# GD_Tcontroller_Sensor.net
KiCad netlist of a schematic drawn in Altium Designer
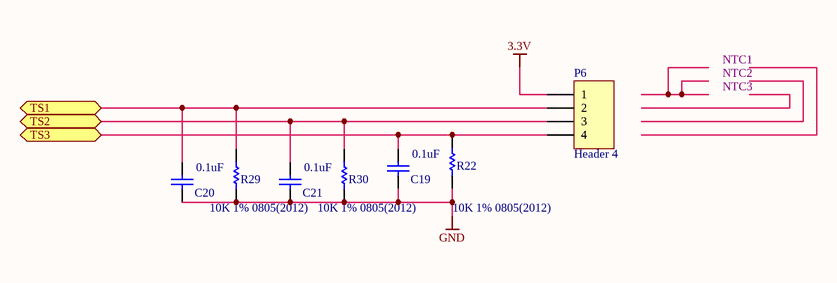
[diagram p0: GD_Tcontroller_Sensor.SchDoc]

(export (version "E")
  (design (tool "Eeschema 10.0.6"))
  (components
    (comp (ref "C19")
      (value "0.1uF")
      (footprint "CAPC0805(2012)100_N")
      (description "CAP 0.1uF 50V ±20% 0805 (2012 Metric) Thickness 1mm SMD")
      (fields (field (name "TOLERANCE") "20%") (field (name "Comment") "CAP 0.1uF 50V 0805(2012)"))
      (libsource (lib "Altium Content Vault") (part "CMP-1036-00070-1"))
    )
    (comp (ref "C20")
      (value "0.1uF")
      (footprint "CAPC0805(2012)100_N")
      (description "CAP 0.1uF 50V ±20% 0805 (2012 Metric) Thickness 1mm SMD")
      (fields (field (name "TOLERANCE") "20%") (field (name "Comment") "CAP 0.1uF 50V 0805(2012)"))
      (libsource (lib "Altium Content Vault") (part "CMP-1036-00070-1"))
    )
    (comp (ref "C21")
      (value "0.1uF")
      (footprint "CAPC0805(2012)100_N")
      (description "CAP 0.1uF 50V ±20% 0805 (2012 Metric) Thickness 1mm SMD")
      (fields (field (name "TOLERANCE") "20%") (field (name "Comment") "CAP 0.1uF 50V 0805(2012)"))
      (libsource (lib "Altium Content Vault") (part "CMP-1036-00070-1"))
    )
    (comp (ref "P6")
      (value "Header 4")
      (footprint "HT5.08-4P-H")
      (description "Header, 4-Pin")
      (fields (field (name "PUBLISHER") "Altium Limited"))
      (libsource (lib "Miscellaneous Connectors") (part "Header 4"))
    )
    (comp (ref "R22")
      (value "10K 1% 0805(2012)")
      (footprint "RESC0805(2012)_L")
      (description "10K 0.125W 5% 0805 (2012 Metric)  SMD")
      (fields (field (name "POWER") "0.125 W") (field (name "TOLERANCE") "1 %"))
      (libsource (lib "Altium Content Vault") (part "CMP-1013-00098-1"))
    )
    (comp (ref "R29")
      (value "10K 1% 0805(2012)")
      (footprint "RESC0805(2012)_L")
      (description "10K 0.125W 5% 0805 (2012 Metric)  SMD")
      (fields (field (name "POWER") "0.125 W") (field (name "TOLERANCE") "1 %"))
      (libsource (lib "Altium Content Vault") (part "CMP-1013-00098-1"))
    )
    (comp (ref "R30")
      (value "10K 1% 0805(2012)")
      (footprint "RESC0805(2012)_L")
      (description "10K 0.125W 5% 0805 (2012 Metric)  SMD")
      (fields (field (name "POWER") "0.125 W") (field (name "TOLERANCE") "1 %"))
      (libsource (lib "Altium Content Vault") (part "CMP-1013-00098-1"))
    )
  )
  (nets
    (net (code "1") (name "/TS1") (class "Default")
      (node (ref "C20") (pin "2") (pinfunction "2_2") (pintype "passive"))
      (node (ref "P6") (pin "2") (pinfunction "2_2") (pintype "passive"))
      (node (ref "R29") (pin "1") (pinfunction "1_1") (pintype "passive"))
    )
    (net (code "2") (name "/TS2") (class "Default")
      (node (ref "C21") (pin "2") (pinfunction "2_2") (pintype "passive"))
      (node (ref "P6") (pin "3") (pinfunction "3_3") (pintype "passive"))
      (node (ref "R30") (pin "1") (pinfunction "1_1") (pintype "passive"))
    )
    (net (code "3") (name "/TS3") (class "Default")
      (node (ref "C19") (pin "2") (pinfunction "2_2") (pintype "passive"))
      (node (ref "P6") (pin "4") (pinfunction "4_4") (pintype "passive"))
      (node (ref "R22") (pin "1") (pinfunction "1_1") (pintype "passive"))
    )
    (net (code "4") (name "3.3V") (class "Default")
      (node (ref "P6") (pin "1") (pinfunction "1_1") (pintype "passive"))
    )
    (net (code "5") (name "GND") (class "Default")
      (node (ref "C19") (pin "1") (pinfunction "1_1") (pintype "passive"))
      (node (ref "C20") (pin "1") (pinfunction "1_1") (pintype "passive"))
      (node (ref "C21") (pin "1") (pinfunction "1_1") (pintype "passive"))
      (node (ref "R22") (pin "2") (pinfunction "2_2") (pintype "passive"))
      (node (ref "R29") (pin "2") (pinfunction "2_2") (pintype "passive"))
      (node (ref "R30") (pin "2") (pinfunction "2_2") (pintype "passive"))
    )
  )
)
